# V_9.net
KiCad netlist of a schematic drawn in Altium Designer
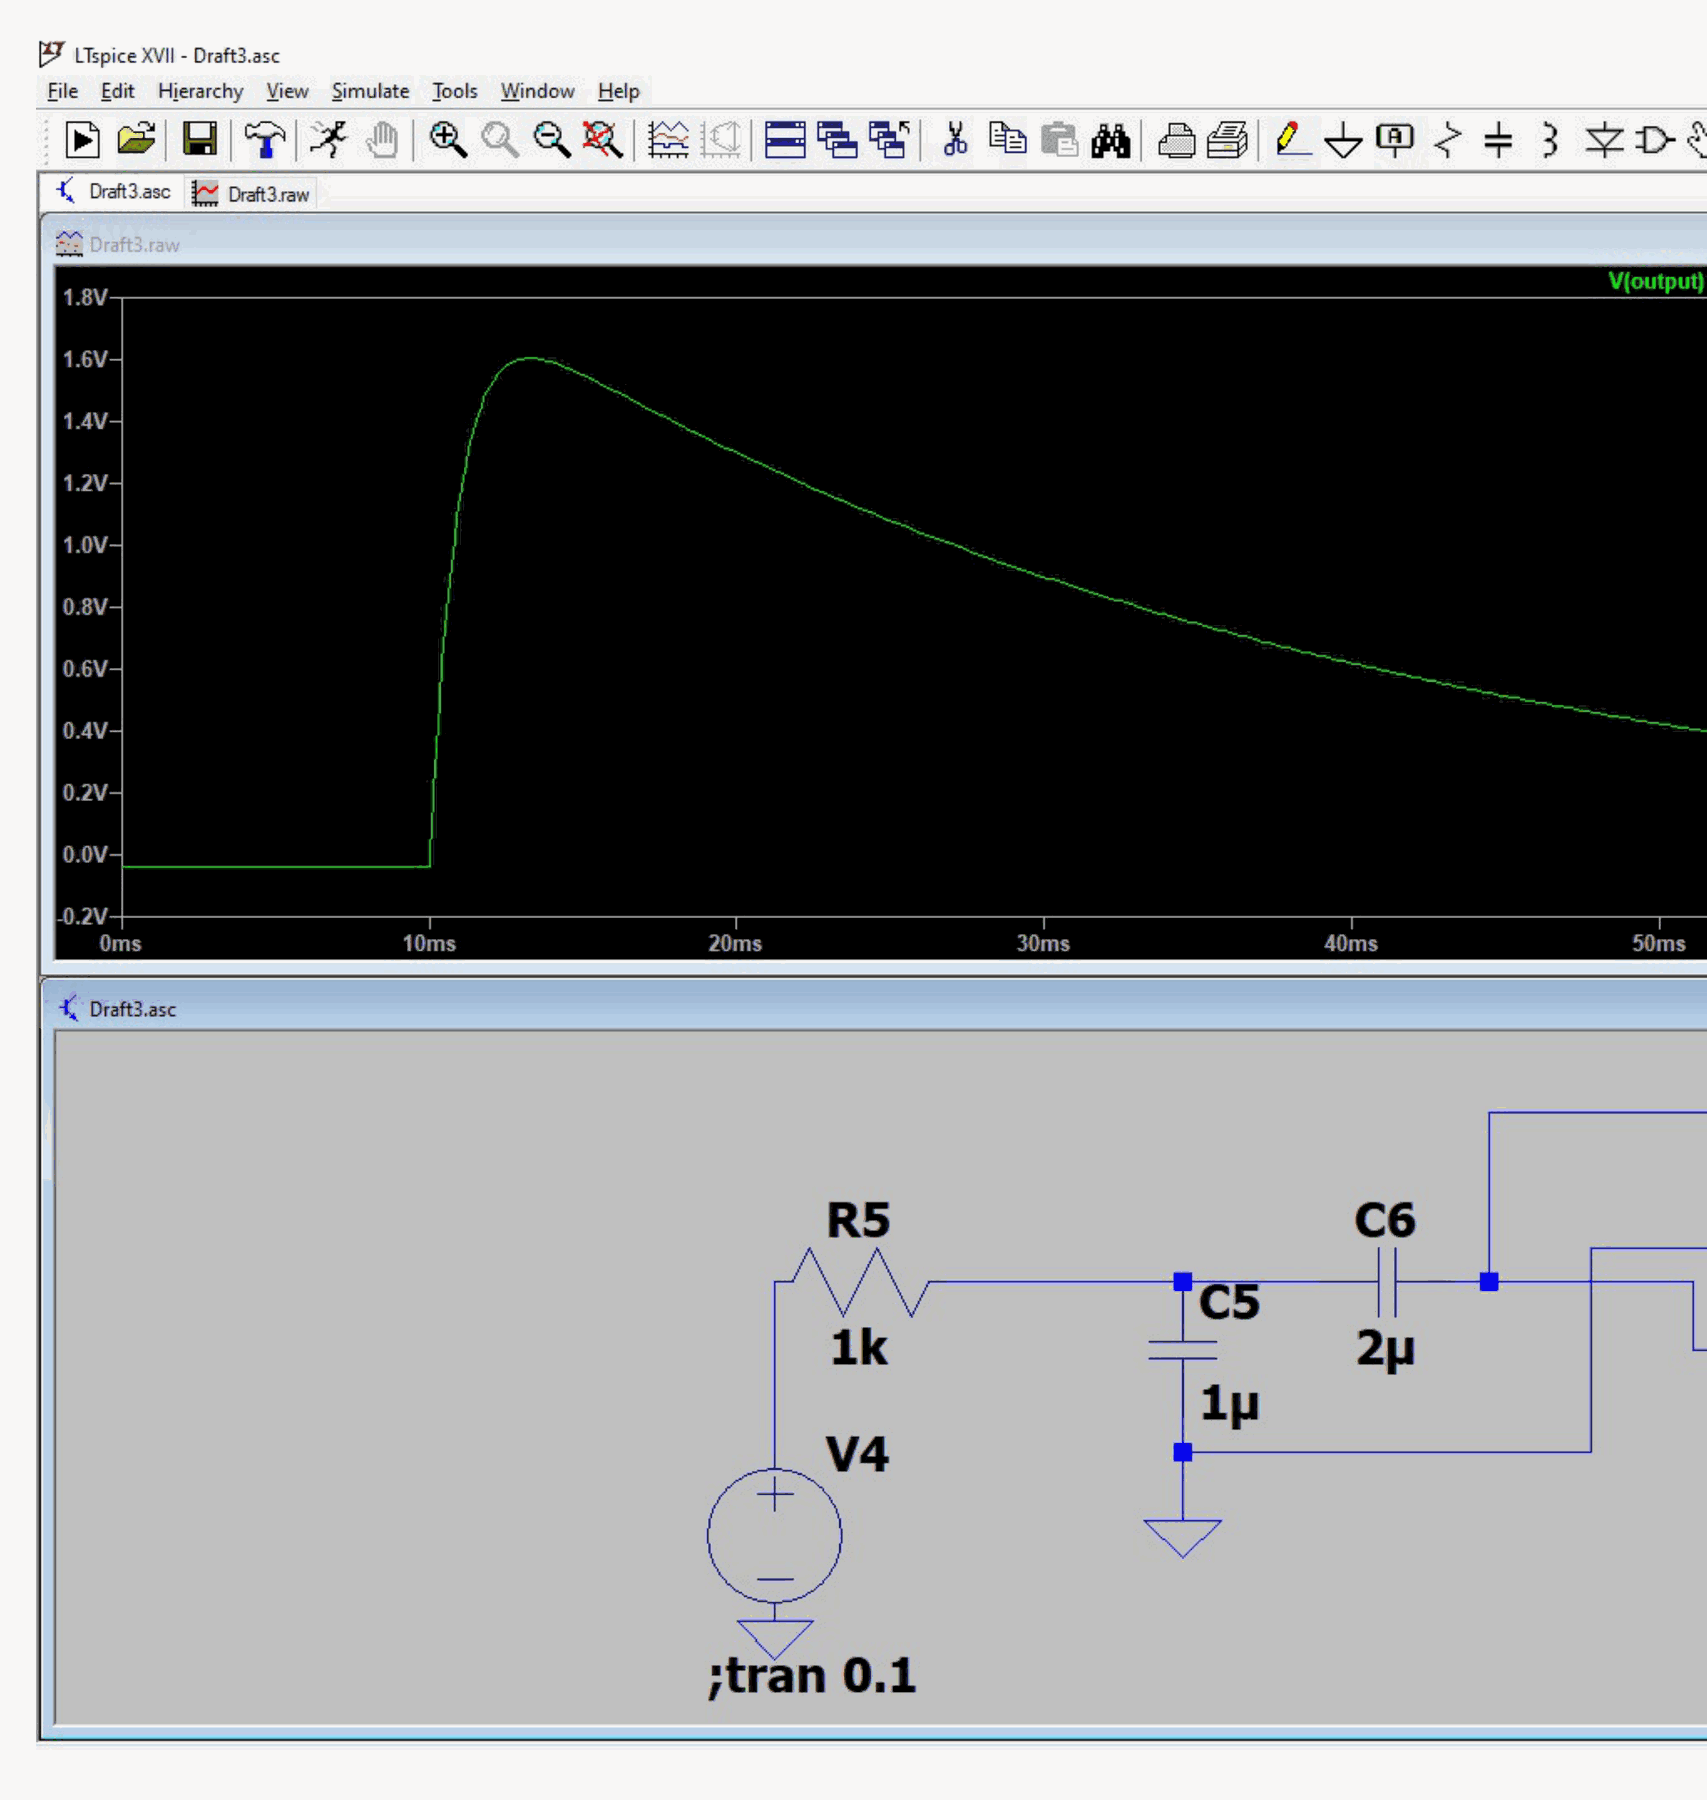
[diagram p0: V_9.SchDoc, top left]
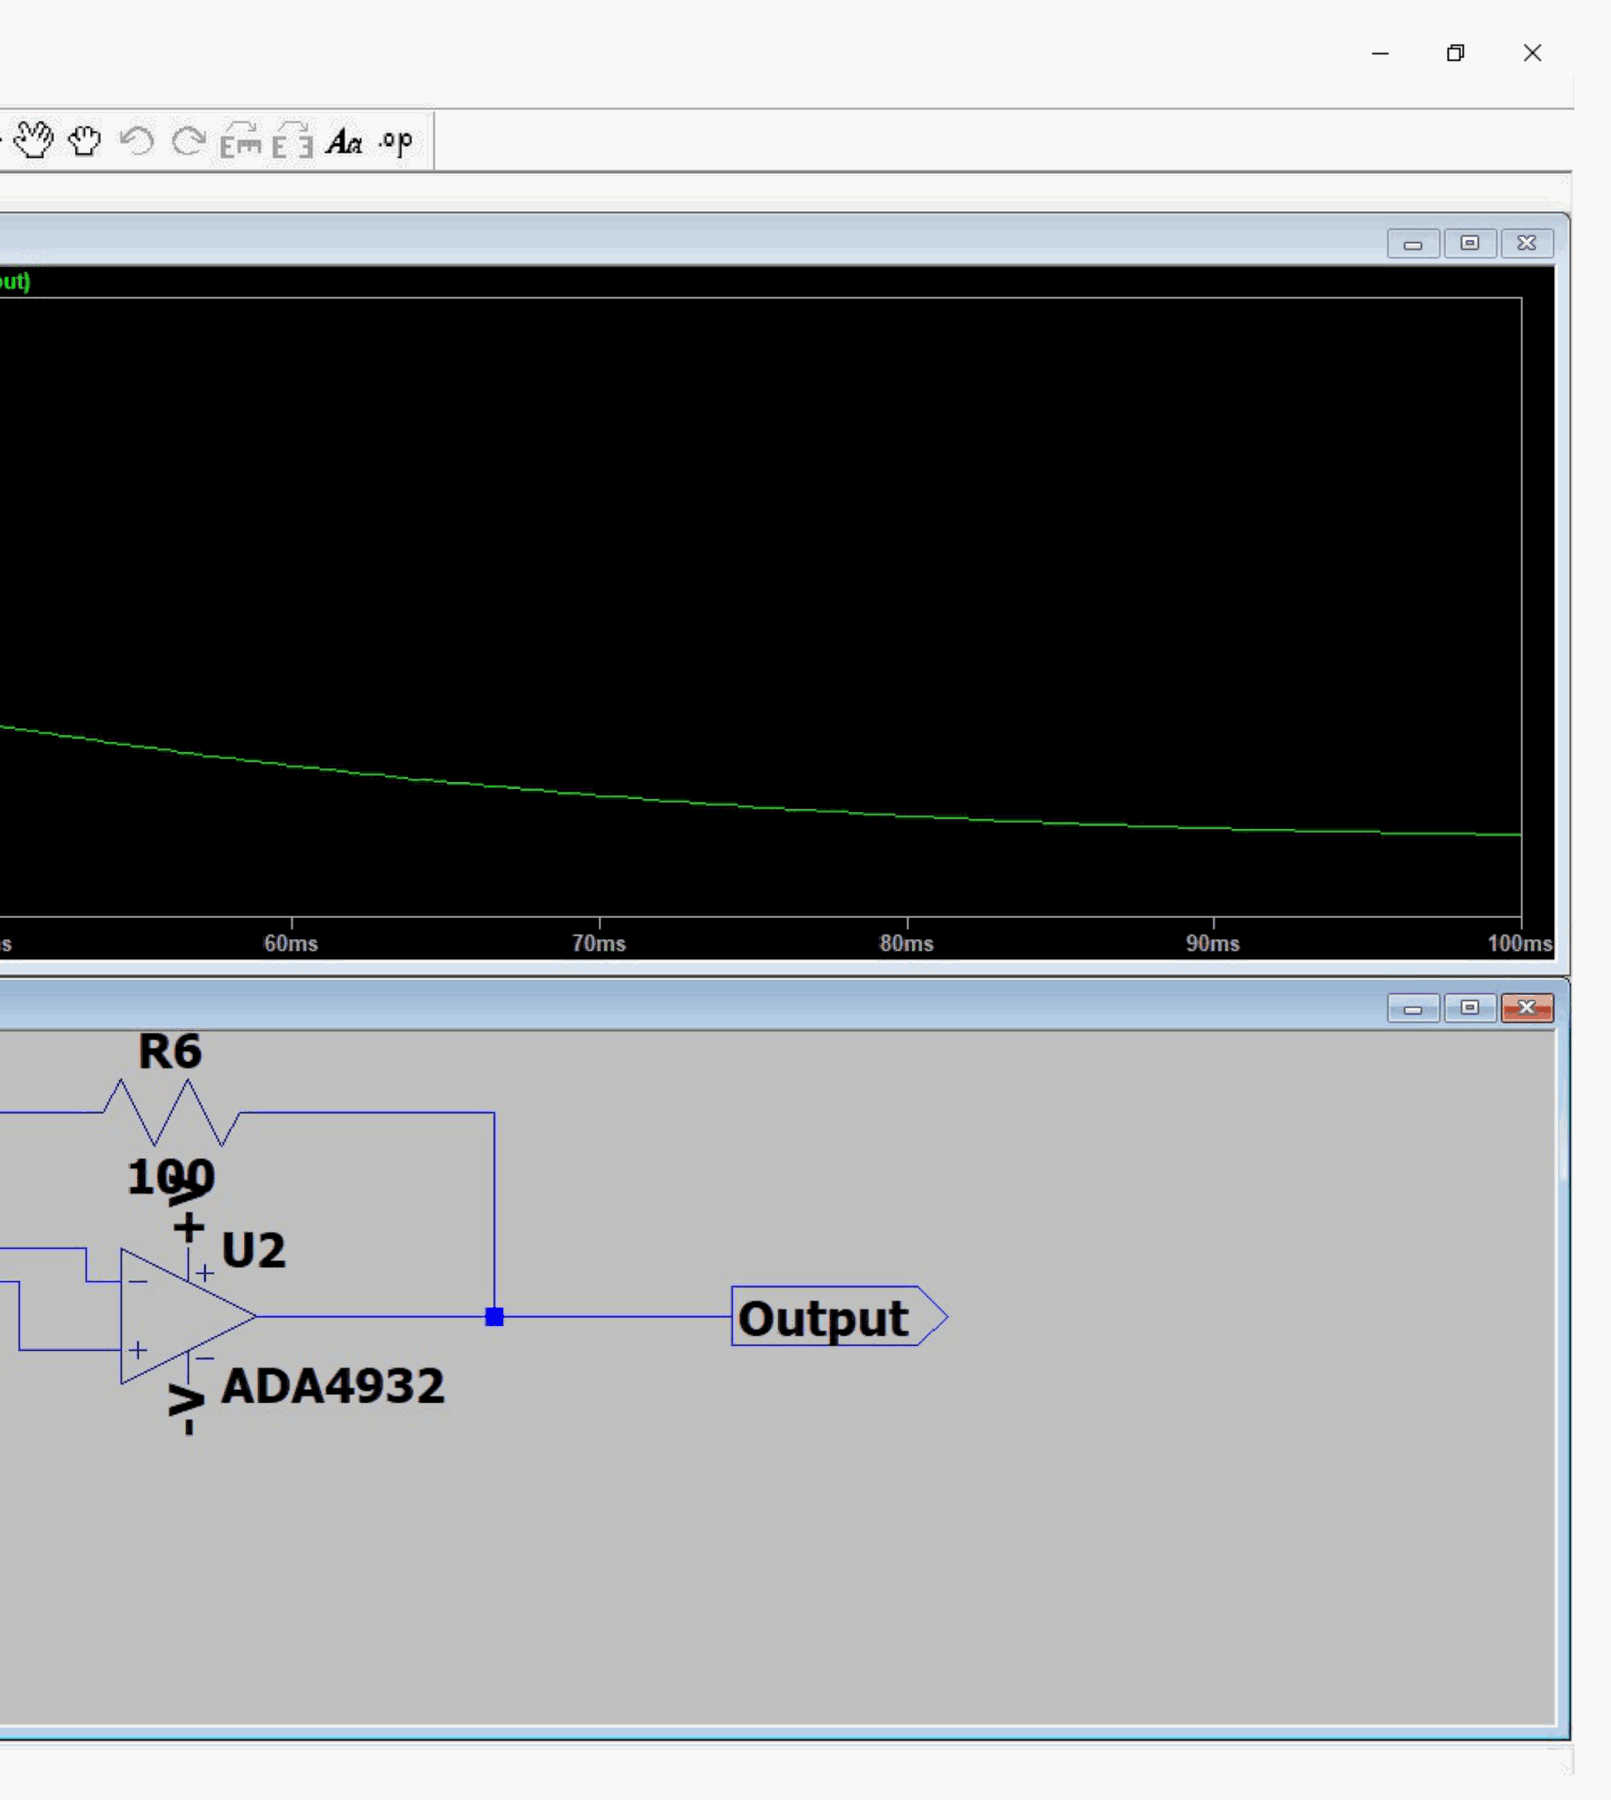
[diagram p1: V_9.SchDoc, top right]
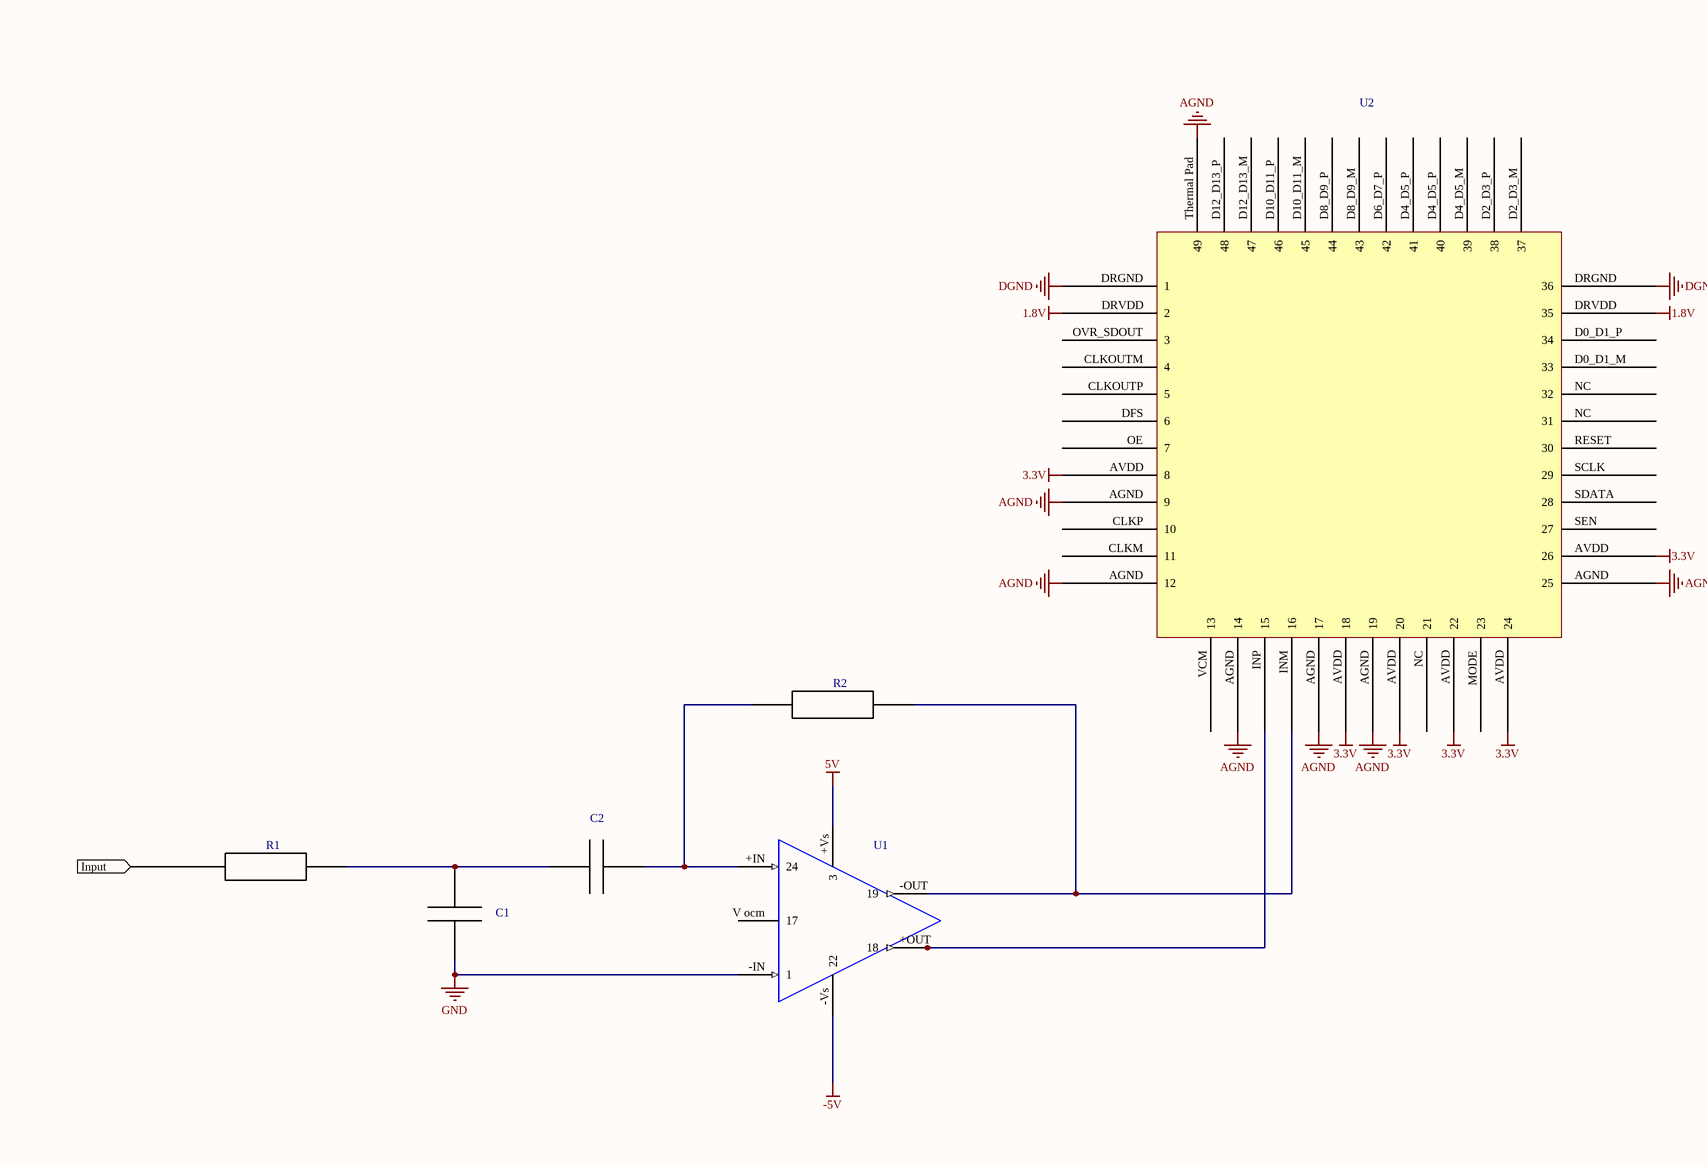
[diagram p2: V_9.SchDoc, bottom left]

(export (version "E")
  (design (tool "Eeschema 10.0.6"))
  (components
    (comp (ref "C1") (value "~") (footprint "C_0805") (libsource (lib "V_6") (part "C")))
    (comp (ref "C2") (value "~") (footprint "C_0805") (libsource (lib "V_6") (part "C")))
    (comp (ref "R1") (value "~") (libsource (lib "V_6") (part "R")))
    (comp (ref "R2") (value "~") (libsource (lib "V_6") (part "R")))
    (comp (ref "U1") (value "~") (footprint "ADA4932-2") (libsource (lib "V_6") (part "ADA4932-2")))
    (comp (ref "U2") (value "~") (footprint "ADS61B49") (libsource (lib "V_6") (part "ADS61B49")))
  )
  (nets
    (net (code "1") (name "-5V") (class "Default")
      (node (ref "U1") (pin "-Vs") (pinfunction "22_-Vs") (pintype "passive"))
    )
    (net (code "2") (name "/Input") (class "Default") (node (ref "R1") (pin "1") (pintype "passive")))
    (net (code "3") (name "1.8V") (class "Default")
      (node (ref "U2") (pin "DRVDD") (pinfunction "2_DRVDD") (pintype "passive"))
    )
    (net (code "4") (name "3.3V") (class "Default")
      (node (ref "U2") (pin "AVDD") (pinfunction "8_AVDD") (pintype "passive"))
    )
    (net (code "5") (name "5V") (class "Default")
      (node (ref "U1") (pin "+Vs") (pinfunction "3_+Vs") (pintype "passive"))
    )
    (net (code "6") (name "AGND") (class "Default")
      (node (ref "U2") (pin "AGND") (pinfunction "9_AGND") (pintype "passive"))
      (node (ref "U2") (pin "Thermal_Pad") (pinfunction "49_Thermal_Pad") (pintype "passive"))
    )
    (net (code "7") (name "DGND") (class "Default")
      (node (ref "U2") (pin "DRGND") (pinfunction "1_DRGND") (pintype "passive"))
    )
    (net (code "8") (name "GND") (class "Default")
      (node (ref "C1") (pin "1") (pintype "passive"))
      (node (ref "U1") (pin "-IN") (pinfunction "1_-IN") (pintype "input"))
    )
    (net (code "9") (name "Net-(C1-Pad2)") (class "Default")
      (node (ref "C1") (pin "2") (pintype "passive"))
      (node (ref "C2") (pin "1") (pintype "passive"))
      (node (ref "R1") (pin "2") (pintype "passive"))
    )
    (net (code "10") (name "Net-(U1-18)") (class "Default")
      (node (ref "U1") (pin "+OUT") (pinfunction "18_+OUT") (pintype "output"))
      (node (ref "U2") (pin "INP") (pinfunction "15_INP") (pintype "passive"))
    )
    (net (code "11") (name "Net-(U1-19)") (class "Default")
      (node (ref "R2") (pin "2") (pintype "passive"))
      (node (ref "U1") (pin "-OUT") (pinfunction "19_-OUT") (pintype "output"))
      (node (ref "U2") (pin "INM") (pinfunction "16_INM") (pintype "passive"))
    )
    (net (code "12") (name "Net-(U1-24)") (class "Default")
      (node (ref "C2") (pin "2") (pintype "passive"))
      (node (ref "R2") (pin "1") (pintype "passive"))
      (node (ref "U1") (pin "+IN") (pinfunction "24_+IN") (pintype "input"))
    )
    (net (code "13") (name "unconnected-(U1-17-PadV_ocm)") (class "Default")
      (node (ref "U1") (pin "V_ocm") (pinfunction "17_V_ocm") (pintype "passive"))
    )
    (net (code "14") (name "unconnected-(U2-3-PadOVR_SDOUT)") (class "Default")
      (node (ref "U2") (pin "OVR_SDOUT") (pinfunction "3_OVR_SDOUT") (pintype "passive"))
    )
    (net (code "15") (name "unconnected-(U2-4-PadCLKOUTM)") (class "Default")
      (node (ref "U2") (pin "CLKOUTM") (pinfunction "4_CLKOUTM") (pintype "passive"))
    )
    (net (code "16") (name "unconnected-(U2-5-PadCLKOUTP)") (class "Default")
      (node (ref "U2") (pin "CLKOUTP") (pinfunction "5_CLKOUTP") (pintype "passive"))
    )
    (net (code "17") (name "unconnected-(U2-6-PadDFS)") (class "Default")
      (node (ref "U2") (pin "DFS") (pinfunction "6_DFS") (pintype "passive"))
    )
    (net (code "18") (name "unconnected-(U2-7-PadOE)") (class "Default")
      (node (ref "U2") (pin "OE") (pinfunction "7_OE") (pintype "passive"))
    )
    (net (code "19") (name "unconnected-(U2-10-PadCLKP)") (class "Default")
      (node (ref "U2") (pin "CLKP") (pinfunction "10_CLKP") (pintype "passive"))
    )
    (net (code "20") (name "unconnected-(U2-11-PadCLKM)") (class "Default")
      (node (ref "U2") (pin "CLKM") (pinfunction "11_CLKM") (pintype "passive"))
    )
    (net (code "21") (name "unconnected-(U2-13-PadVCM)") (class "Default")
      (node (ref "U2") (pin "VCM") (pinfunction "13_VCM") (pintype "passive"))
    )
    (net (code "22") (name "unconnected-(U2-21-PadNC)") (class "Default")
      (node (ref "U2") (pin "NC") (pinfunction "21_NC") (pintype "passive"))
    )
    (net (code "23") (name "unconnected-(U2-23-PadMODE)") (class "Default")
      (node (ref "U2") (pin "MODE") (pinfunction "23_MODE") (pintype "passive"))
    )
    (net (code "24") (name "unconnected-(U2-27-PadSEN)") (class "Default")
      (node (ref "U2") (pin "SEN") (pinfunction "27_SEN") (pintype "passive"))
    )
    (net (code "25") (name "unconnected-(U2-28-PadSDATA)") (class "Default")
      (node (ref "U2") (pin "SDATA") (pinfunction "28_SDATA") (pintype "passive"))
    )
    (net (code "26") (name "unconnected-(U2-29-PadSCLK)") (class "Default")
      (node (ref "U2") (pin "SCLK") (pinfunction "29_SCLK") (pintype "passive"))
    )
    (net (code "27") (name "unconnected-(U2-30-PadRESET)") (class "Default")
      (node (ref "U2") (pin "RESET") (pinfunction "30_RESET") (pintype "passive"))
    )
    (net (code "28") (name "unconnected-(U2-31-PadNC)") (class "Default")
      (node (ref "U2") (pin "NC") (pinfunction "31_NC") (pintype "passive"))
    )
    (net (code "29") (name "unconnected-(U2-32-PadNC)") (class "Default")
      (node (ref "U2") (pin "NC") (pinfunction "32_NC") (pintype "passive"))
    )
    (net (code "30") (name "unconnected-(U2-33-PadD0_D1_M)") (class "Default")
      (node (ref "U2") (pin "D0_D1_M") (pinfunction "33_D0_D1_M") (pintype "passive"))
    )
    (net (code "31") (name "unconnected-(U2-34-PadD0_D1_P)") (class "Default")
      (node (ref "U2") (pin "D0_D1_P") (pinfunction "34_D0_D1_P") (pintype "passive"))
    )
    (net (code "32") (name "unconnected-(U2-37-PadD2_D3_M)") (class "Default")
      (node (ref "U2") (pin "D2_D3_M") (pinfunction "37_D2_D3_M") (pintype "passive"))
    )
    (net (code "33") (name "unconnected-(U2-38-PadD2_D3_P)") (class "Default")
      (node (ref "U2") (pin "D2_D3_P") (pinfunction "38_D2_D3_P") (pintype "passive"))
    )
    (net (code "34") (name "unconnected-(U2-39-PadD4_D5_M)") (class "Default")
      (node (ref "U2") (pin "D4_D5_M") (pinfunction "39_D4_D5_M") (pintype "passive"))
    )
    (net (code "35") (name "unconnected-(U2-40-PadD4_D5_P)") (class "Default")
      (node (ref "U2") (pin "D4_D5_P") (pinfunction "40_D4_D5_P") (pintype "passive"))
    )
    (net (code "36") (name "unconnected-(U2-41-PadD4_D5_P)") (class "Default")
      (node (ref "U2") (pin "D4_D5_P") (pinfunction "41_D4_D5_P") (pintype "passive"))
    )
    (net (code "37") (name "unconnected-(U2-42-PadD6_D7_P)") (class "Default")
      (node (ref "U2") (pin "D6_D7_P") (pinfunction "42_D6_D7_P") (pintype "passive"))
    )
    (net (code "38") (name "unconnected-(U2-43-PadD8_D9_M)") (class "Default")
      (node (ref "U2") (pin "D8_D9_M") (pinfunction "43_D8_D9_M") (pintype "passive"))
    )
    (net (code "39") (name "unconnected-(U2-44-PadD8_D9_P)") (class "Default")
      (node (ref "U2") (pin "D8_D9_P") (pinfunction "44_D8_D9_P") (pintype "passive"))
    )
    (net (code "40") (name "unconnected-(U2-45-PadD10_D11_M)") (class "Default")
      (node (ref "U2") (pin "D10_D11_M") (pinfunction "45_D10_D11_M") (pintype "passive"))
    )
    (net (code "41") (name "unconnected-(U2-46-PadD10_D11_P)") (class "Default")
      (node (ref "U2") (pin "D10_D11_P") (pinfunction "46_D10_D11_P") (pintype "passive"))
    )
    (net (code "42") (name "unconnected-(U2-47-PadD12_D13_M)") (class "Default")
      (node (ref "U2") (pin "D12_D13_M") (pinfunction "47_D12_D13_M") (pintype "passive"))
    )
    (net (code "43") (name "unconnected-(U2-48-PadD12_D13_P)") (class "Default")
      (node (ref "U2") (pin "D12_D13_P") (pinfunction "48_D12_D13_P") (pintype "passive"))
    )
  )
)
